# Series_I_power.net
KiCad netlist of a schematic drawn in EAGLE
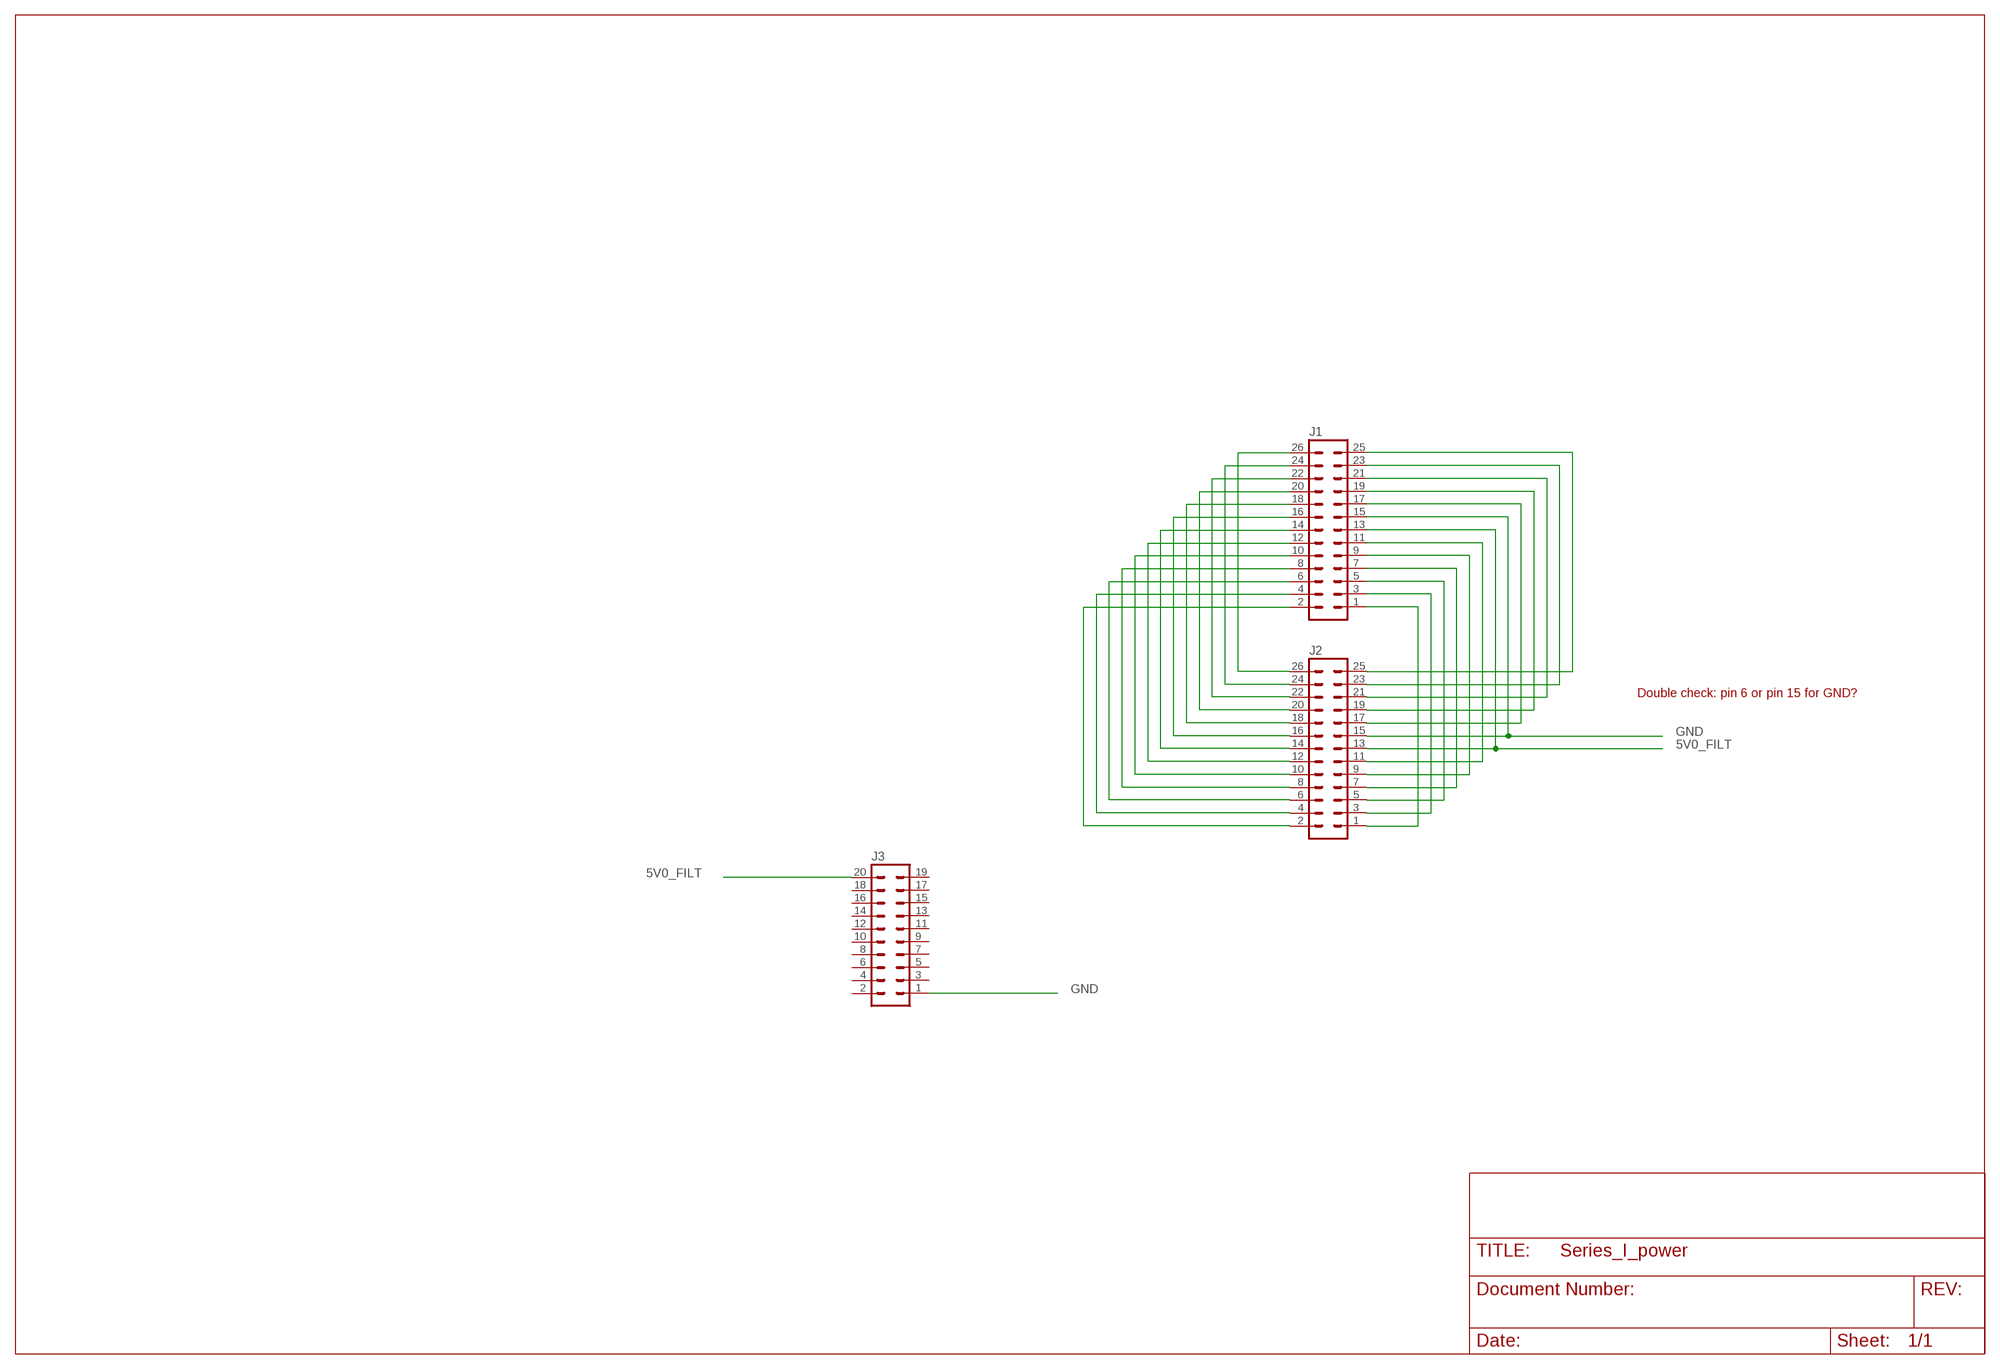
[diagram p0: schematic, sheet 1]

(export (version "E")
  (design (tool "Eeschema 10.0.6"))
  (components
    (comp (ref "J1")
      (value "26H")
      (footprint "eagle-import:26H")
      (libsource (lib "eagle-import") (part "26H"))
    )
    (comp (ref "J2")
      (value "26H")
      (footprint "eagle-import:26H")
      (libsource (lib "eagle-import") (part "26H"))
    )
    (comp (ref "J3")
      (value "ML20")
      (footprint "eagle-import:ML20")
      (libsource (lib "eagle-import") (part "ML20"))
    )
  )
  (nets
    (net (code "1") (name "/5V0_FILT") (class "Default")
      (node (ref "J1") (pin "13") (pinfunction "13_13") (pintype "passive"))
      (node (ref "J2") (pin "13") (pinfunction "13_13") (pintype "passive"))
      (node (ref "J3") (pin "20") (pinfunction "20_20") (pintype "passive"))
    )
    (net (code "2") (name "/GND") (class "Default")
      (node (ref "J1") (pin "15") (pinfunction "15_15") (pintype "passive"))
      (node (ref "J2") (pin "15") (pinfunction "15_15") (pintype "passive"))
      (node (ref "J3") (pin "1") (pinfunction "1_1") (pintype "passive"))
    )
    (net (code "3") (name "Net-(J1-Pad1)") (class "Default")
      (node (ref "J1") (pin "1") (pinfunction "1_1") (pintype "passive"))
      (node (ref "J2") (pin "1") (pinfunction "1_1") (pintype "passive"))
    )
    (net (code "4") (name "Net-(J1-Pad2)") (class "Default")
      (node (ref "J1") (pin "2") (pinfunction "2_2") (pintype "passive"))
      (node (ref "J2") (pin "2") (pinfunction "2_2") (pintype "passive"))
    )
    (net (code "5") (name "Net-(J1-Pad3)") (class "Default")
      (node (ref "J1") (pin "3") (pinfunction "3_3") (pintype "passive"))
      (node (ref "J2") (pin "3") (pinfunction "3_3") (pintype "passive"))
    )
    (net (code "6") (name "Net-(J1-Pad4)") (class "Default")
      (node (ref "J1") (pin "4") (pinfunction "4_4") (pintype "passive"))
      (node (ref "J2") (pin "4") (pinfunction "4_4") (pintype "passive"))
    )
    (net (code "7") (name "Net-(J1-Pad5)") (class "Default")
      (node (ref "J1") (pin "5") (pinfunction "5_5") (pintype "passive"))
      (node (ref "J2") (pin "5") (pinfunction "5_5") (pintype "passive"))
    )
    (net (code "8") (name "Net-(J1-Pad6)") (class "Default")
      (node (ref "J1") (pin "6") (pinfunction "6_6") (pintype "passive"))
      (node (ref "J2") (pin "6") (pinfunction "6_6") (pintype "passive"))
    )
    (net (code "9") (name "Net-(J1-Pad7)") (class "Default")
      (node (ref "J1") (pin "7") (pinfunction "7_7") (pintype "passive"))
      (node (ref "J2") (pin "7") (pinfunction "7_7") (pintype "passive"))
    )
    (net (code "10") (name "Net-(J1-Pad8)") (class "Default")
      (node (ref "J1") (pin "8") (pinfunction "8_8") (pintype "passive"))
      (node (ref "J2") (pin "8") (pinfunction "8_8") (pintype "passive"))
    )
    (net (code "11") (name "Net-(J1-Pad9)") (class "Default")
      (node (ref "J1") (pin "9") (pinfunction "9_9") (pintype "passive"))
      (node (ref "J2") (pin "9") (pinfunction "9_9") (pintype "passive"))
    )
    (net (code "12") (name "Net-(J1-Pad10)") (class "Default")
      (node (ref "J1") (pin "10") (pinfunction "10_10") (pintype "passive"))
      (node (ref "J2") (pin "10") (pinfunction "10_10") (pintype "passive"))
    )
    (net (code "13") (name "Net-(J1-Pad11)") (class "Default")
      (node (ref "J1") (pin "11") (pinfunction "11_11") (pintype "passive"))
      (node (ref "J2") (pin "11") (pinfunction "11_11") (pintype "passive"))
    )
    (net (code "14") (name "Net-(J1-Pad12)") (class "Default")
      (node (ref "J1") (pin "12") (pinfunction "12_12") (pintype "passive"))
      (node (ref "J2") (pin "12") (pinfunction "12_12") (pintype "passive"))
    )
    (net (code "15") (name "Net-(J1-Pad14)") (class "Default")
      (node (ref "J1") (pin "14") (pinfunction "14_14") (pintype "passive"))
      (node (ref "J2") (pin "14") (pinfunction "14_14") (pintype "passive"))
    )
    (net (code "16") (name "Net-(J1-Pad16)") (class "Default")
      (node (ref "J1") (pin "16") (pinfunction "16_16") (pintype "passive"))
      (node (ref "J2") (pin "16") (pinfunction "16_16") (pintype "passive"))
    )
    (net (code "17") (name "Net-(J1-Pad17)") (class "Default")
      (node (ref "J1") (pin "17") (pinfunction "17_17") (pintype "passive"))
      (node (ref "J2") (pin "17") (pinfunction "17_17") (pintype "passive"))
    )
    (net (code "18") (name "Net-(J1-Pad18)") (class "Default")
      (node (ref "J1") (pin "18") (pinfunction "18_18") (pintype "passive"))
      (node (ref "J2") (pin "18") (pinfunction "18_18") (pintype "passive"))
    )
    (net (code "19") (name "Net-(J1-Pad19)") (class "Default")
      (node (ref "J1") (pin "19") (pinfunction "19_19") (pintype "passive"))
      (node (ref "J2") (pin "19") (pinfunction "19_19") (pintype "passive"))
    )
    (net (code "20") (name "Net-(J1-Pad20)") (class "Default")
      (node (ref "J1") (pin "20") (pinfunction "20_20") (pintype "passive"))
      (node (ref "J2") (pin "20") (pinfunction "20_20") (pintype "passive"))
    )
    (net (code "21") (name "Net-(J1-Pad21)") (class "Default")
      (node (ref "J1") (pin "21") (pinfunction "21_21") (pintype "passive"))
      (node (ref "J2") (pin "21") (pinfunction "21_21") (pintype "passive"))
    )
    (net (code "22") (name "Net-(J1-Pad22)") (class "Default")
      (node (ref "J1") (pin "22") (pinfunction "22_22") (pintype "passive"))
      (node (ref "J2") (pin "22") (pinfunction "22_22") (pintype "passive"))
    )
    (net (code "23") (name "Net-(J1-Pad23)") (class "Default")
      (node (ref "J1") (pin "23") (pinfunction "23_23") (pintype "passive"))
      (node (ref "J2") (pin "23") (pinfunction "23_23") (pintype "passive"))
    )
    (net (code "24") (name "Net-(J1-Pad24)") (class "Default")
      (node (ref "J1") (pin "24") (pinfunction "24_24") (pintype "passive"))
      (node (ref "J2") (pin "24") (pinfunction "24_24") (pintype "passive"))
    )
    (net (code "25") (name "Net-(J1-Pad25)") (class "Default")
      (node (ref "J1") (pin "25") (pinfunction "25_25") (pintype "passive"))
      (node (ref "J2") (pin "25") (pinfunction "25_25") (pintype "passive"))
    )
    (net (code "26") (name "Net-(J1-Pad26)") (class "Default")
      (node (ref "J1") (pin "26") (pinfunction "26_26") (pintype "passive"))
      (node (ref "J2") (pin "26") (pinfunction "26_26") (pintype "passive"))
    )
    (net (code "27") (name "unconnected-(J3-Pad2)") (class "Default")
      (node (ref "J3") (pin "2") (pinfunction "2_2") (pintype "passive"))
    )
    (net (code "28") (name "unconnected-(J3-Pad3)") (class "Default")
      (node (ref "J3") (pin "3") (pinfunction "3_3") (pintype "passive"))
    )
    (net (code "29") (name "unconnected-(J3-Pad4)") (class "Default")
      (node (ref "J3") (pin "4") (pinfunction "4_4") (pintype "passive"))
    )
    (net (code "30") (name "unconnected-(J3-Pad5)") (class "Default")
      (node (ref "J3") (pin "5") (pinfunction "5_5") (pintype "passive"))
    )
    (net (code "31") (name "unconnected-(J3-Pad6)") (class "Default")
      (node (ref "J3") (pin "6") (pinfunction "6_6") (pintype "passive"))
    )
    (net (code "32") (name "unconnected-(J3-Pad7)") (class "Default")
      (node (ref "J3") (pin "7") (pinfunction "7_7") (pintype "passive"))
    )
    (net (code "33") (name "unconnected-(J3-Pad8)") (class "Default")
      (node (ref "J3") (pin "8") (pinfunction "8_8") (pintype "passive"))
    )
    (net (code "34") (name "unconnected-(J3-Pad9)") (class "Default")
      (node (ref "J3") (pin "9") (pinfunction "9_9") (pintype "passive"))
    )
    (net (code "35") (name "unconnected-(J3-Pad10)") (class "Default")
      (node (ref "J3") (pin "10") (pinfunction "10_10") (pintype "passive"))
    )
    (net (code "36") (name "unconnected-(J3-Pad11)") (class "Default")
      (node (ref "J3") (pin "11") (pinfunction "11_11") (pintype "passive"))
    )
    (net (code "37") (name "unconnected-(J3-Pad12)") (class "Default")
      (node (ref "J3") (pin "12") (pinfunction "12_12") (pintype "passive"))
    )
    (net (code "38") (name "unconnected-(J3-Pad13)") (class "Default")
      (node (ref "J3") (pin "13") (pinfunction "13_13") (pintype "passive"))
    )
    (net (code "39") (name "unconnected-(J3-Pad14)") (class "Default")
      (node (ref "J3") (pin "14") (pinfunction "14_14") (pintype "passive"))
    )
    (net (code "40") (name "unconnected-(J3-Pad15)") (class "Default")
      (node (ref "J3") (pin "15") (pinfunction "15_15") (pintype "passive"))
    )
    (net (code "41") (name "unconnected-(J3-Pad16)") (class "Default")
      (node (ref "J3") (pin "16") (pinfunction "16_16") (pintype "passive"))
    )
    (net (code "42") (name "unconnected-(J3-Pad17)") (class "Default")
      (node (ref "J3") (pin "17") (pinfunction "17_17") (pintype "passive"))
    )
    (net (code "43") (name "unconnected-(J3-Pad18)") (class "Default")
      (node (ref "J3") (pin "18") (pinfunction "18_18") (pintype "passive"))
    )
    (net (code "44") (name "unconnected-(J3-Pad19)") (class "Default")
      (node (ref "J3") (pin "19") (pinfunction "19_19") (pintype "passive"))
    )
  )
)
